# NCP1200.net
KiCad netlist of a schematic drawn in EAGLE
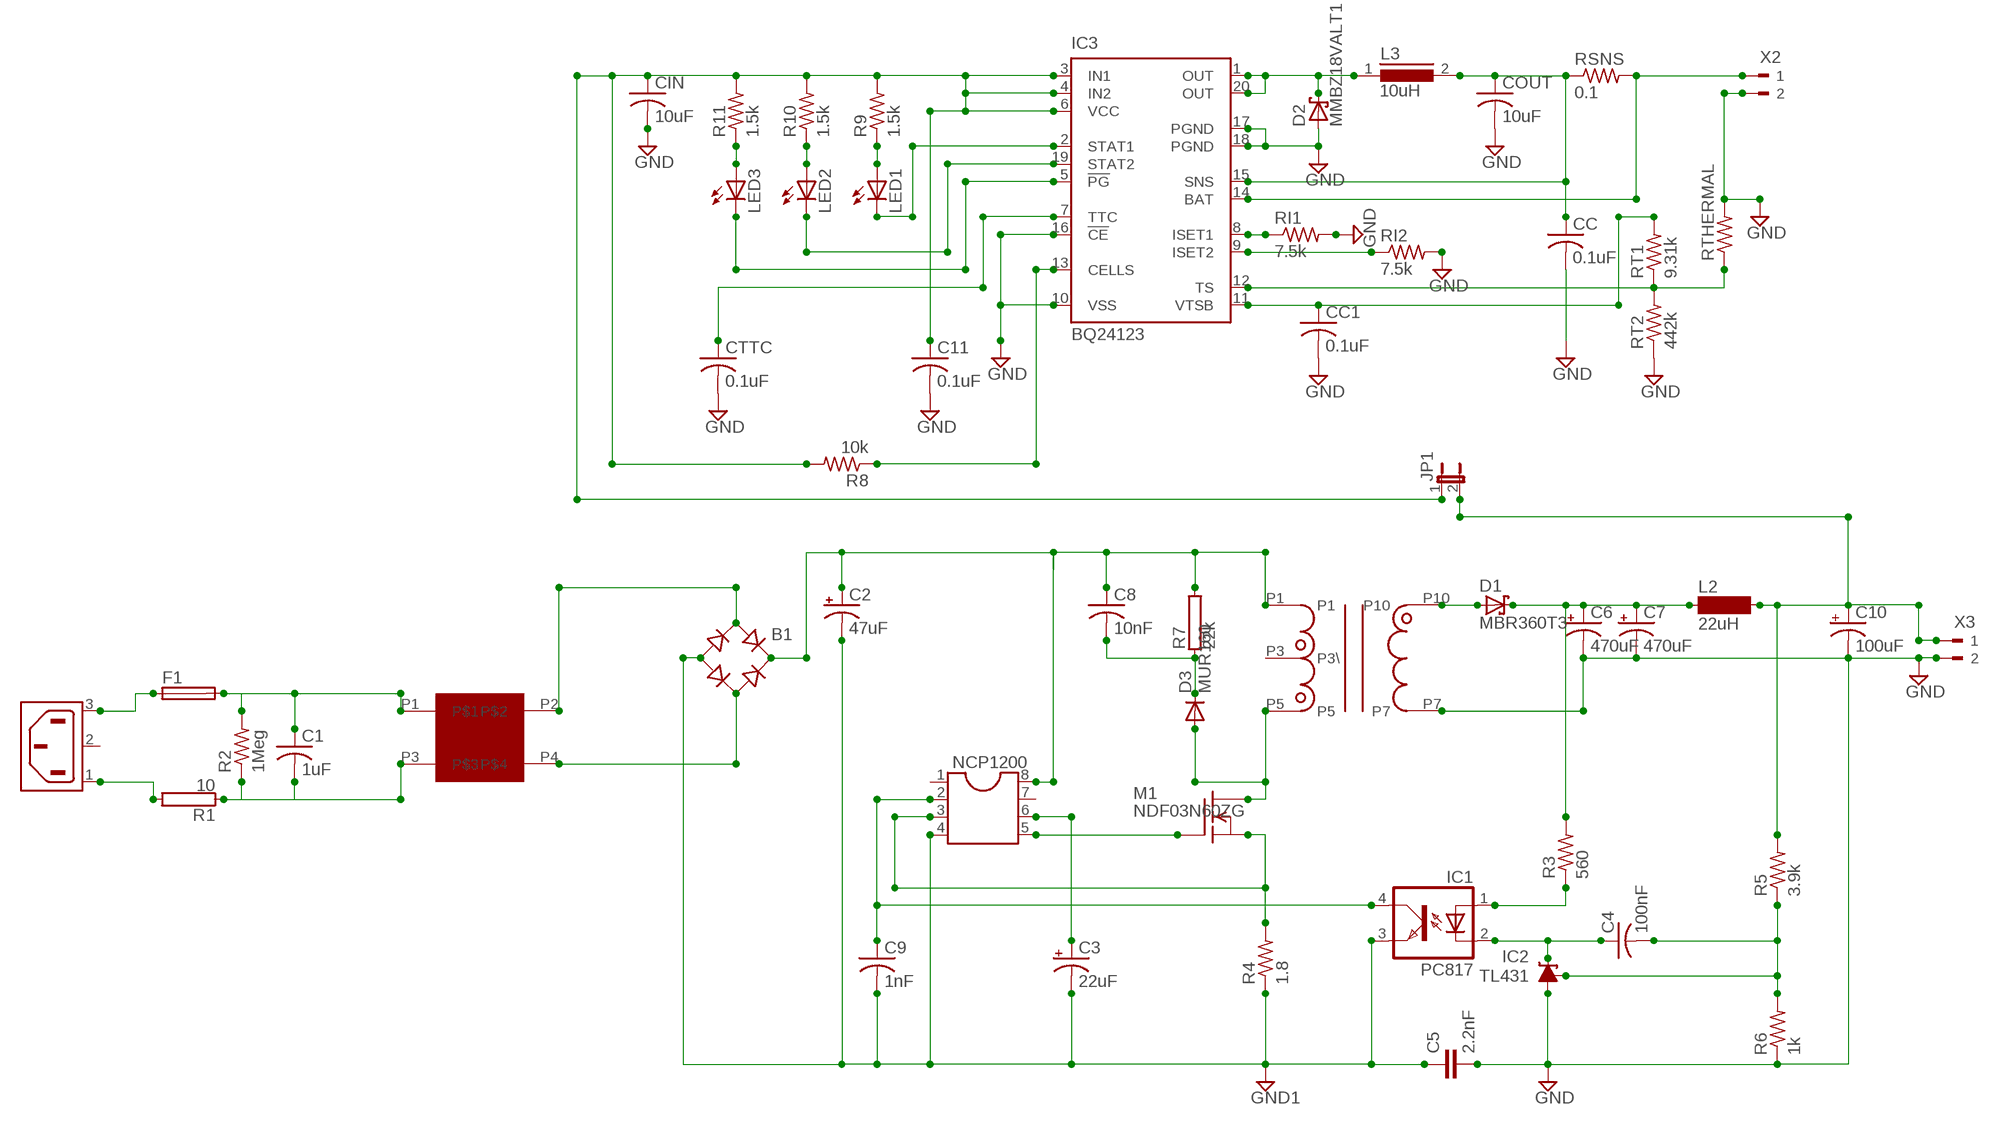
[diagram p0: schematic, sheet 1]

(export (version "E")
  (design (tool "Eeschema 10.0.6"))
  (components
    (comp (ref "B1")
      (value "B-DIL")
      (footprint "eagle-import:B-DIL")
      (libsource (lib "eagle-import") (part "B-DIL"))
    )
    (comp (ref "C1")
      (value "1uF")
      (footprint "eagle-import:C150-091X182")
      (libsource (lib "eagle-import") (part "C-US150-091X182"))
    )
    (comp (ref "C2")
      (value "47uF")
      (footprint "eagle-import:EB22,5D")
      (libsource (lib "eagle-import") (part "CPOL-USE10-22.5"))
    )
    (comp (ref "C3")
      (value "22uF")
      (footprint "eagle-import:E5-5")
      (libsource (lib "eagle-import") (part "CPOL-USE5-5"))
    )
    (comp (ref "C4")
      (value "100nF")
      (footprint "eagle-import:C0805")
      (libsource (lib "eagle-import") (part "C-USC0805"))
    )
    (comp (ref "C5")
      (value "2.2nF")
      (footprint "eagle-import:YC10B4")
      (libsource (lib "eagle-import") (part "CYYC10B4"))
    )
    (comp (ref "C6")
      (value "470uF")
      (footprint "eagle-import:E5-10,5")
      (libsource (lib "eagle-import") (part "CPOL-USE5-10.5"))
    )
    (comp (ref "C7")
      (value "470uF")
      (footprint "eagle-import:E5-10,5")
      (libsource (lib "eagle-import") (part "CPOL-USE5-10.5"))
    )
    (comp (ref "C8")
      (value "10nF")
      (footprint "eagle-import:C102-064X133")
      (libsource (lib "eagle-import") (part "C-US102-064X133"))
    )
    (comp (ref "C9")
      (value "1nF")
      (footprint "eagle-import:C0805")
      (libsource (lib "eagle-import") (part "C-USC0805"))
    )
    (comp (ref "C10")
      (value "100uF")
      (footprint "eagle-import:E2,5-6")
      (libsource (lib "eagle-import") (part "CPOL-USE2.5-6"))
    )
    (comp (ref "C11")
      (value "0.1uF")
      (footprint "eagle-import:C0805")
      (libsource (lib "eagle-import") (part "C-USC0805"))
    )
    (comp (ref "CC")
      (value "0.1uF")
      (footprint "eagle-import:C0805")
      (libsource (lib "eagle-import") (part "C-USC0805"))
    )
    (comp (ref "CC1")
      (value "0.1uF")
      (footprint "eagle-import:C0805")
      (libsource (lib "eagle-import") (part "C-USC0805"))
    )
    (comp (ref "CIN")
      (value "10uF")
      (footprint "eagle-import:C0805")
      (libsource (lib "eagle-import") (part "C-USC0805"))
    )
    (comp (ref "COUT")
      (value "10uF")
      (footprint "eagle-import:C0805")
      (libsource (lib "eagle-import") (part "C-USC0805"))
    )
    (comp (ref "CTTC")
      (value "0.1uF")
      (footprint "eagle-import:C0805")
      (libsource (lib "eagle-import") (part "C-USC0805"))
    )
    (comp (ref "D1")
      (value "MBR360T3")
      (footprint "eagle-import:SMB")
      (libsource (lib "eagle-import") (part "MBRS130LT3"))
    )
    (comp (ref "D2")
      (value "MMBZ18VALT1")
      (footprint "eagle-import:C4111-15")
      (libsource (lib "eagle-import") (part "1N5908"))
    )
    (comp (ref "D3")
      (value "MUR160")
      (footprint "eagle-import:SGA-10")
      (libsource (lib "eagle-import") (part "BY203"))
    )
    (comp (ref "F1")
      (value "SH25")
      (footprint "eagle-import:SH25")
      (fields (field (name "MF") "SCHURTER") (field (name "MPN") "0031.8211"))
      (libsource (lib "eagle-import") (part "SH25"))
    )
    (comp (ref "IC1")
      (value "PC817")
      (footprint "eagle-import:DIL04")
      (fields (field (name "MPN") "PC817X4J000F"))
      (libsource (lib "eagle-import") (part "PC817"))
    )
    (comp (ref "IC2")
      (value "TL431")
      (footprint "eagle-import:LP_O-PBCY-W3")
      (libsource (lib "eagle-import") (part "LM4041ILPB"))
    )
    (comp (ref "IC3")
      (value "BQ24123")
      (footprint "eagle-import:QFN20_3,5X4,5")
      (fields (field (name "MPN") "BQ24123RHLT"))
      (libsource (lib "eagle-import") (part "BQ24123"))
    )
    (comp (ref "JP1")
      (value "JP1E")
      (footprint "eagle-import:JP1")
      (libsource (lib "eagle-import") (part "JP1E"))
    )
    (comp (ref "L2")
      (value "22uH")
      (footprint "eagle-import:SD8")
      (libsource (lib "eagle-import") (part "SD8"))
    )
    (comp (ref "L3")
      (value "10uH")
      (footprint "eagle-import:DR73")
      (libsource (lib "eagle-import") (part "DR73"))
    )
    (comp (ref "LED1")
      (value "SFH482")
      (footprint "eagle-import:SFH482")
      (libsource (lib "eagle-import") (part "SFH482"))
    )
    (comp (ref "LED2")
      (value "SFH482")
      (footprint "eagle-import:SFH482")
      (libsource (lib "eagle-import") (part "SFH482"))
    )
    (comp (ref "LED3")
      (value "SFH482")
      (footprint "eagle-import:SFH482")
      (libsource (lib "eagle-import") (part "SFH482"))
    )
    (comp (ref "M1")
      (value "NDF03N60ZG")
      (footprint "eagle-import:TO220")
      (libsource (lib "eagle-import") (part "BUZ20"))
    )
    (comp (ref "NCP1200")
      (value "DIL8")
      (footprint "eagle-import:DIL08")
      (libsource (lib "eagle-import") (part "DIL8"))
    )
    (comp (ref "R1")
      (value "10")
      (footprint "eagle-import:KH206-8")
      (libsource (lib "eagle-import") (part "RKH206-8"))
    )
    (comp (ref "R2")
      (value "1Meg")
      (footprint "eagle-import:R0805")
      (libsource (lib "eagle-import") (part "R-US_R0805"))
    )
    (comp (ref "R3")
      (value "560")
      (footprint "eagle-import:R0805")
      (libsource (lib "eagle-import") (part "R-US_R0805"))
    )
    (comp (ref "R4")
      (value "1.8")
      (footprint "eagle-import:R1206")
      (libsource (lib "eagle-import") (part "R-US_R1206"))
    )
    (comp (ref "R5")
      (value "3.9k")
      (footprint "eagle-import:R0805")
      (libsource (lib "eagle-import") (part "R-US_R0805"))
    )
    (comp (ref "R6")
      (value "1k")
      (footprint "eagle-import:R0805")
      (libsource (lib "eagle-import") (part "R-US_R0805"))
    )
    (comp (ref "R7")
      (value "22k")
      (footprint "eagle-import:KH206-8")
      (libsource (lib "eagle-import") (part "RKH206-8"))
    )
    (comp (ref "R8")
      (value "10k")
      (footprint "eagle-import:R0805")
      (libsource (lib "eagle-import") (part "R-US_R0805"))
    )
    (comp (ref "R9")
      (value "1.5k")
      (footprint "eagle-import:R0805")
      (libsource (lib "eagle-import") (part "R-US_R0805"))
    )
    (comp (ref "R10")
      (value "1.5k")
      (footprint "eagle-import:R0805")
      (libsource (lib "eagle-import") (part "R-US_R0805"))
    )
    (comp (ref "R11")
      (value "1.5k")
      (footprint "eagle-import:R0805")
      (libsource (lib "eagle-import") (part "R-US_R0805"))
    )
    (comp (ref "RI1")
      (value "7.5k")
      (footprint "eagle-import:R0805")
      (libsource (lib "eagle-import") (part "R-US_R0805"))
    )
    (comp (ref "RI2")
      (value "7.5k")
      (footprint "eagle-import:R0805")
      (libsource (lib "eagle-import") (part "R-US_R0805"))
    )
    (comp (ref "RSNS")
      (value "0.1")
      (footprint "eagle-import:R1206")
      (libsource (lib "eagle-import") (part "R-US_R1206"))
    )
    (comp (ref "RT1")
      (value "9.31k")
      (footprint "eagle-import:R0805")
      (libsource (lib "eagle-import") (part "R-US_R0805"))
    )
    (comp (ref "RT2")
      (value "442k")
      (footprint "eagle-import:R0805")
      (libsource (lib "eagle-import") (part "R-US_R0805"))
    )
    (comp (ref "RTHERMAL")
      (value "R-US_R0805")
      (footprint "eagle-import:R0805")
      (libsource (lib "eagle-import") (part "R-US_R0805"))
    )
    (comp (ref "U$1")
      (value "RENCO1")
      (footprint "eagle-import:RENCO1")
      (libsource (lib "eagle-import") (part "RENCO1"))
    )
    (comp (ref "U$2")
      (value "L1CHO5")
      (footprint "eagle-import:L1CHO")
      (libsource (lib "eagle-import") (part "L1CHO5"))
    )
    (comp (ref "X1")
      (value "6ESRM-P")
      (footprint "eagle-import:6ESRM-P")
      (fields (field (name "MF") "TYCO ELECTRONICS"))
      (libsource (lib "eagle-import") (part "6ESRM-P"))
    )
    (comp (ref "X2")
      (value "90-2")
      (footprint "eagle-import:90-2")
      (libsource (lib "eagle-import") (part "90-2"))
    )
    (comp (ref "X3")
      (value "90-2")
      (footprint "eagle-import:90-2")
      (fields (field (name "OC_FARNELL") "unknown") (field (name "OC_NEWARK") "unknown"))
      (libsource (lib "eagle-import") (part "90-2"))
    )
  )
  (nets
    (net (code "1") (name "GND") (class "Default")
      (node (ref "C10") (pin "-") (pinfunction "-_-") (pintype "passive"))
      (node (ref "C11") (pin "2") (pinfunction "2_2") (pintype "passive"))
      (node (ref "C5") (pin "2") (pinfunction "2_2") (pintype "passive"))
      (node (ref "C6") (pin "-") (pinfunction "-_-") (pintype "passive"))
      (node (ref "C7") (pin "-") (pinfunction "-_-") (pintype "passive"))
      (node (ref "CC") (pin "2") (pinfunction "2_2") (pintype "passive"))
      (node (ref "CC1") (pin "2") (pinfunction "2_2") (pintype "passive"))
      (node (ref "CIN") (pin "2") (pinfunction "2_2") (pintype "passive"))
      (node (ref "COUT") (pin "2") (pinfunction "2_2") (pintype "passive"))
      (node (ref "CTTC") (pin "2") (pinfunction "2_2") (pintype "passive"))
      (node (ref "D2") (pin "A") (pinfunction "A_A") (pintype "passive"))
      (node (ref "IC2") (pin "3") (pinfunction "A_3") (pintype "passive"))
      (node (ref "IC3") (pin "10") (pinfunction "VSS_10") (pintype "power_in"))
      (node (ref "IC3") (pin "16") (pinfunction "~{CE}_16") (pintype "input"))
      (node (ref "IC3") (pin "17") (pinfunction "PGND_17") (pintype "input"))
      (node (ref "IC3") (pin "18") (pinfunction "PGND_18") (pintype "input"))
      (node (ref "R6") (pin "1") (pinfunction "1_1") (pintype "passive"))
      (node (ref "RI1") (pin "2") (pinfunction "2_2") (pintype "passive"))
      (node (ref "RI2") (pin "2") (pinfunction "2_2") (pintype "passive"))
      (node (ref "RT2") (pin "1") (pinfunction "1_1") (pintype "passive"))
      (node (ref "RTHERMAL") (pin "2") (pinfunction "2_2") (pintype "passive"))
      (node (ref "U$1") (pin "P7") (pinfunction "P7_P7") (pintype "bidirectional"))
      (node (ref "X2") (pin "2") (pinfunction "2_2") (pintype "passive"))
      (node (ref "X3") (pin "2") (pinfunction "2_2") (pintype "passive"))
    )
    (net (code "2") (name "GND1") (class "Default")
      (node (ref "B1") (pin "-") (pinfunction "-_-") (pintype "passive"))
      (node (ref "C2") (pin "-") (pinfunction "-_-") (pintype "passive"))
      (node (ref "C3") (pin "-") (pinfunction "-_-") (pintype "passive"))
      (node (ref "C5") (pin "1") (pinfunction "1_1") (pintype "passive"))
      (node (ref "C9") (pin "2") (pinfunction "2_2") (pintype "passive"))
      (node (ref "IC1") (pin "3") (pinfunction "EMIT_3") (pintype "passive"))
      (node (ref "NCP1200") (pin "4") (pinfunction "4_4") (pintype "passive"))
      (node (ref "R4") (pin "1") (pinfunction "1_1") (pintype "passive"))
    )
    (net (code "3") (name "Net-(B1-Pad+)") (class "Default")
      (node (ref "B1") (pin "+") (pinfunction "+_+") (pintype "passive"))
      (node (ref "C2") (pin "+") (pinfunction "+_+") (pintype "passive"))
      (node (ref "C8") (pin "1") (pinfunction "1_1") (pintype "passive"))
      (node (ref "NCP1200") (pin "8") (pinfunction "8_8") (pintype "passive"))
      (node (ref "R7") (pin "2") (pinfunction "2_2") (pintype "passive"))
      (node (ref "U$1") (pin "P1") (pinfunction "P1_P1") (pintype "bidirectional"))
    )
    (net (code "4") (name "Net-(C3-Pad+)") (class "Default")
      (node (ref "C3") (pin "+") (pinfunction "+_+") (pintype "passive"))
      (node (ref "NCP1200") (pin "6") (pinfunction "6_6") (pintype "passive"))
    )
    (net (code "5") (name "Net-(C6-Pad+)") (class "Default")
      (node (ref "C6") (pin "+") (pinfunction "+_+") (pintype "passive"))
      (node (ref "C7") (pin "+") (pinfunction "+_+") (pintype "passive"))
      (node (ref "D1") (pin "C") (pinfunction "C_C") (pintype "passive"))
      (node (ref "L2") (pin "1") (pinfunction "1_1") (pintype "passive"))
      (node (ref "R3") (pin "2") (pinfunction "2_2") (pintype "passive"))
    )
    (net (code "6") (name "Net-(C8-Pad2)") (class "Default")
      (node (ref "C8") (pin "2") (pinfunction "2_2") (pintype "passive"))
      (node (ref "D3") (pin "C") (pinfunction "C_C") (pintype "passive"))
      (node (ref "R7") (pin "1") (pinfunction "1_1") (pintype "passive"))
    )
    (net (code "7") (name "Net-(C10-Pad+)") (class "Default")
      (node (ref "C10") (pin "+") (pinfunction "+_+") (pintype "passive"))
      (node (ref "JP1") (pin "2") (pinfunction "2_2") (pintype "passive"))
      (node (ref "L2") (pin "2") (pinfunction "2_2") (pintype "passive"))
      (node (ref "R5") (pin "2") (pinfunction "2_2") (pintype "passive"))
      (node (ref "X3") (pin "1") (pinfunction "1_1") (pintype "passive"))
    )
    (net (code "8") (name "Net-(D1-PadA)") (class "Default")
      (node (ref "D1") (pin "A") (pinfunction "A_A") (pintype "passive"))
      (node (ref "U$1") (pin "P10") (pinfunction "P10_P10") (pintype "bidirectional"))
    )
    (net (code "9") (name "Net-(D2-PadC)") (class "Default")
      (node (ref "D2") (pin "C") (pinfunction "C_C") (pintype "passive"))
      (node (ref "IC3") (pin "1") (pinfunction "OUT_1") (pintype "output"))
      (node (ref "IC3") (pin "20") (pinfunction "OUT_20") (pintype "input"))
      (node (ref "L3") (pin "1") (pinfunction "1_1") (pintype "passive"))
    )
    (net (code "10") (name "Net-(IC1-A)") (class "Default")
      (node (ref "IC1") (pin "1") (pinfunction "A_1") (pintype "passive"))
      (node (ref "R3") (pin "1") (pinfunction "1_1") (pintype "passive"))
    )
    (net (code "11") (name "Net-(IC1-C)") (class "Default")
      (node (ref "C4") (pin "1") (pinfunction "1_1") (pintype "passive"))
      (node (ref "IC1") (pin "2") (pinfunction "C_2") (pintype "passive"))
      (node (ref "IC2") (pin "2") (pinfunction "C_2") (pintype "passive"))
    )
    (net (code "12") (name "Net-(IC1-COL)") (class "Default")
      (node (ref "C9") (pin "1") (pinfunction "1_1") (pintype "passive"))
      (node (ref "IC1") (pin "4") (pinfunction "COL_4") (pintype "passive"))
      (node (ref "NCP1200") (pin "2") (pinfunction "2_2") (pintype "passive"))
    )
    (net (code "13") (name "Net-(IC2-FB)") (class "Default")
      (node (ref "C4") (pin "2") (pinfunction "2_2") (pintype "passive"))
      (node (ref "IC2") (pin "1") (pinfunction "FB_1") (pintype "passive"))
      (node (ref "R5") (pin "1") (pinfunction "1_1") (pintype "passive"))
      (node (ref "R6") (pin "2") (pinfunction "2_2") (pintype "passive"))
    )
    (net (code "14") (name "Net-(IC3B-BAT)") (class "Default")
      (node (ref "IC3") (pin "14") (pinfunction "BAT_14") (pintype "input"))
      (node (ref "RSNS") (pin "2") (pinfunction "2_2") (pintype "passive"))
      (node (ref "X2") (pin "1") (pinfunction "1_1") (pintype "passive"))
    )
    (net (code "15") (name "Net-(IC3B-CELLS)") (class "Default")
      (node (ref "IC3") (pin "13") (pinfunction "CELLS_13") (pintype "input"))
      (node (ref "R8") (pin "1") (pinfunction "1_1") (pintype "passive"))
    )
    (net (code "16") (name "Net-(IC3B-IN1)") (class "Default")
      (node (ref "C11") (pin "1") (pinfunction "1_1") (pintype "passive"))
      (node (ref "CIN") (pin "1") (pinfunction "1_1") (pintype "passive"))
      (node (ref "IC3") (pin "3") (pinfunction "IN1_3") (pintype "input"))
      (node (ref "IC3") (pin "4") (pinfunction "IN2_4") (pintype "input"))
      (node (ref "IC3") (pin "6") (pinfunction "VCC_6") (pintype "input"))
      (node (ref "JP1") (pin "1") (pinfunction "1_1") (pintype "passive"))
      (node (ref "R10") (pin "2") (pinfunction "2_2") (pintype "passive"))
      (node (ref "R11") (pin "2") (pinfunction "2_2") (pintype "passive"))
      (node (ref "R8") (pin "2") (pinfunction "2_2") (pintype "passive"))
      (node (ref "R9") (pin "2") (pinfunction "2_2") (pintype "passive"))
    )
    (net (code "17") (name "Net-(IC3B-ISET1)") (class "Default")
      (node (ref "IC3") (pin "8") (pinfunction "ISET1_8") (pintype "bidirectional"))
      (node (ref "RI1") (pin "1") (pinfunction "1_1") (pintype "passive"))
    )
    (net (code "18") (name "Net-(IC3B-ISET2)") (class "Default")
      (node (ref "IC3") (pin "9") (pinfunction "ISET2_9") (pintype "bidirectional"))
      (node (ref "RI2") (pin "1") (pinfunction "1_1") (pintype "passive"))
    )
    (net (code "19") (name "Net-(IC3B-SNS)") (class "Default")
      (node (ref "CC") (pin "1") (pinfunction "1_1") (pintype "passive"))
      (node (ref "COUT") (pin "1") (pinfunction "1_1") (pintype "passive"))
      (node (ref "IC3") (pin "15") (pinfunction "SNS_15") (pintype "input"))
      (node (ref "L3") (pin "2") (pinfunction "2_2") (pintype "passive"))
      (node (ref "RSNS") (pin "1") (pinfunction "1_1") (pintype "passive"))
    )
    (net (code "20") (name "Net-(IC3B-STAT1)") (class "Default")
      (node (ref "IC3") (pin "2") (pinfunction "STAT1_2") (pintype "output"))
      (node (ref "LED1") (pin "K") (pinfunction "C_K") (pintype "passive"))
    )
    (net (code "21") (name "Net-(IC3B-STAT2)") (class "Default")
      (node (ref "IC3") (pin "19") (pinfunction "STAT2_19") (pintype "output"))
      (node (ref "LED2") (pin "K") (pinfunction "C_K") (pintype "passive"))
    )
    (net (code "22") (name "Net-(IC3B-TS)") (class "Default")
      (node (ref "IC3") (pin "12") (pinfunction "TS_12") (pintype "input"))
      (node (ref "RT1") (pin "1") (pinfunction "1_1") (pintype "passive"))
      (node (ref "RT2") (pin "2") (pinfunction "2_2") (pintype "passive"))
      (node (ref "RTHERMAL") (pin "1") (pinfunction "1_1") (pintype "passive"))
    )
    (net (code "23") (name "Net-(IC3B-TTC)") (class "Default")
      (node (ref "CTTC") (pin "1") (pinfunction "1_1") (pintype "passive"))
      (node (ref "IC3") (pin "7") (pinfunction "TTC_7") (pintype "passive"))
    )
    (net (code "24") (name "Net-(IC3B-VTSB)") (class "Default")
      (node (ref "CC1") (pin "1") (pinfunction "1_1") (pintype "passive"))
      (node (ref "IC3") (pin "11") (pinfunction "VTSB_11") (pintype "output"))
      (node (ref "RT1") (pin "2") (pinfunction "2_2") (pintype "passive"))
    )
    (net (code "25") (name "Net-(IC3B-~{PG})") (class "Default")
      (node (ref "IC3") (pin "5") (pinfunction "~{PG}_5") (pintype "output"))
      (node (ref "LED3") (pin "K") (pinfunction "C_K") (pintype "passive"))
    )
    (net (code "26") (name "Net-(LED1-PadA)") (class "Default")
      (node (ref "LED1") (pin "A") (pinfunction "A_A") (pintype "passive"))
      (node (ref "R9") (pin "1") (pinfunction "1_1") (pintype "passive"))
    )
    (net (code "27") (name "Net-(LED2-PadA)") (class "Default")
      (node (ref "LED2") (pin "A") (pinfunction "A_A") (pintype "passive"))
      (node (ref "R10") (pin "1") (pinfunction "1_1") (pintype "passive"))
    )
    (net (code "28") (name "Net-(LED3-PadA)") (class "Default")
      (node (ref "LED3") (pin "A") (pinfunction "A_A") (pintype "passive"))
      (node (ref "R11") (pin "1") (pinfunction "1_1") (pintype "passive"))
    )
    (net (code "29") (name "Net-(M1-D)") (class "Default")
      (node (ref "D3") (pin "A") (pinfunction "A_A") (pintype "passive"))
      (node (ref "M1") (pin "2") (pinfunction "D_2") (pintype "passive"))
      (node (ref "U$1") (pin "P5") (pinfunction "P5_P5") (pintype "bidirectional"))
    )
    (net (code "30") (name "Net-(M1-G)") (class "Default")
      (node (ref "M1") (pin "1") (pinfunction "G_1") (pintype "passive"))
      (node (ref "NCP1200") (pin "5") (pinfunction "5_5") (pintype "passive"))
    )
    (net (code "31") (name "Net-(M1-S)") (class "Default")
      (node (ref "M1") (pin "3") (pinfunction "S_3") (pintype "passive"))
      (node (ref "NCP1200") (pin "3") (pinfunction "3_3") (pintype "passive"))
      (node (ref "R4") (pin "2") (pinfunction "2_2") (pintype "passive"))
    )
    (net (code "32") (name "Net-(U$2-P$1)") (class "Default")
      (node (ref "C1") (pin "1") (pinfunction "1_1") (pintype "passive"))
      (node (ref "F1") (pin "2") (pinfunction "2_2") (pintype "passive"))
      (node (ref "R2") (pin "2") (pinfunction "2_2") (pintype "passive"))
      (node (ref "U$2") (pin "P1") (pinfunction "P$1_P1") (pintype "bidirectional"))
    )
    (net (code "33") (name "Net-(U$2-P$2)") (class "Default")
      (node (ref "B1") (pin "AC1") (pinfunction "AC1_AC1") (pintype "passive"))
      (node (ref "U$2") (pin "P2") (pinfunction "P$2_P2") (pintype "bidirectional"))
    )
    (net (code "34") (name "Net-(U$2-P$3)") (class "Default")
      (node (ref "C1") (pin "2") (pinfunction "2_2") (pintype "passive"))
      (node (ref "R1") (pin "1") (pinfunction "1_1") (pintype "passive"))
      (node (ref "R2") (pin "1") (pinfunction "1_1") (pintype "passive"))
      (node (ref "U$2") (pin "P3") (pinfunction "P$3_P3") (pintype "bidirectional"))
    )
    (net (code "35") (name "Net-(U$2-P$4)") (class "Default")
      (node (ref "B1") (pin "AC2") (pinfunction "AC2_AC2") (pintype "passive"))
      (node (ref "U$2") (pin "P4") (pinfunction "P$4_P4") (pintype "bidirectional"))
    )
    (net (code "36") (name "Net-(X1-AC1)") (class "Default")
      (node (ref "R1") (pin "2") (pinfunction "2_2") (pintype "passive"))
      (node (ref "X1") (pin "1") (pinfunction "AC1_1") (pintype "passive"))
    )
    (net (code "37") (name "Net-(X1-AC2)") (class "Default")
      (node (ref "F1") (pin "1") (pinfunction "1_1") (pintype "passive"))
      (node (ref "X1") (pin "3") (pinfunction "AC2_3") (pintype "passive"))
    )
    (net (code "38") (name "unconnected-(NCP1200-Pad1)") (class "Default")
      (node (ref "NCP1200") (pin "1") (pinfunction "1_1") (pintype "passive"))
    )
    (net (code "39") (name "unconnected-(NCP1200-Pad7)") (class "Default")
      (node (ref "NCP1200") (pin "7") (pinfunction "7_7") (pintype "passive"))
    )
    (net (code "40") (name "unconnected-(U$1-P3\\-PadP3)") (class "Default")
      (node (ref "U$1") (pin "P3") (pinfunction "P3\\_P3") (pintype "bidirectional"))
    )
    (net (code "41") (name "unconnected-(X1-SH-Pad2)") (class "Default")
      (node (ref "X1") (pin "2") (pinfunction "SH_2") (pintype "passive"))
    )
  )
)
